# 14-Cypress.net
KiCad netlist of a schematic drawn in Altium Designer
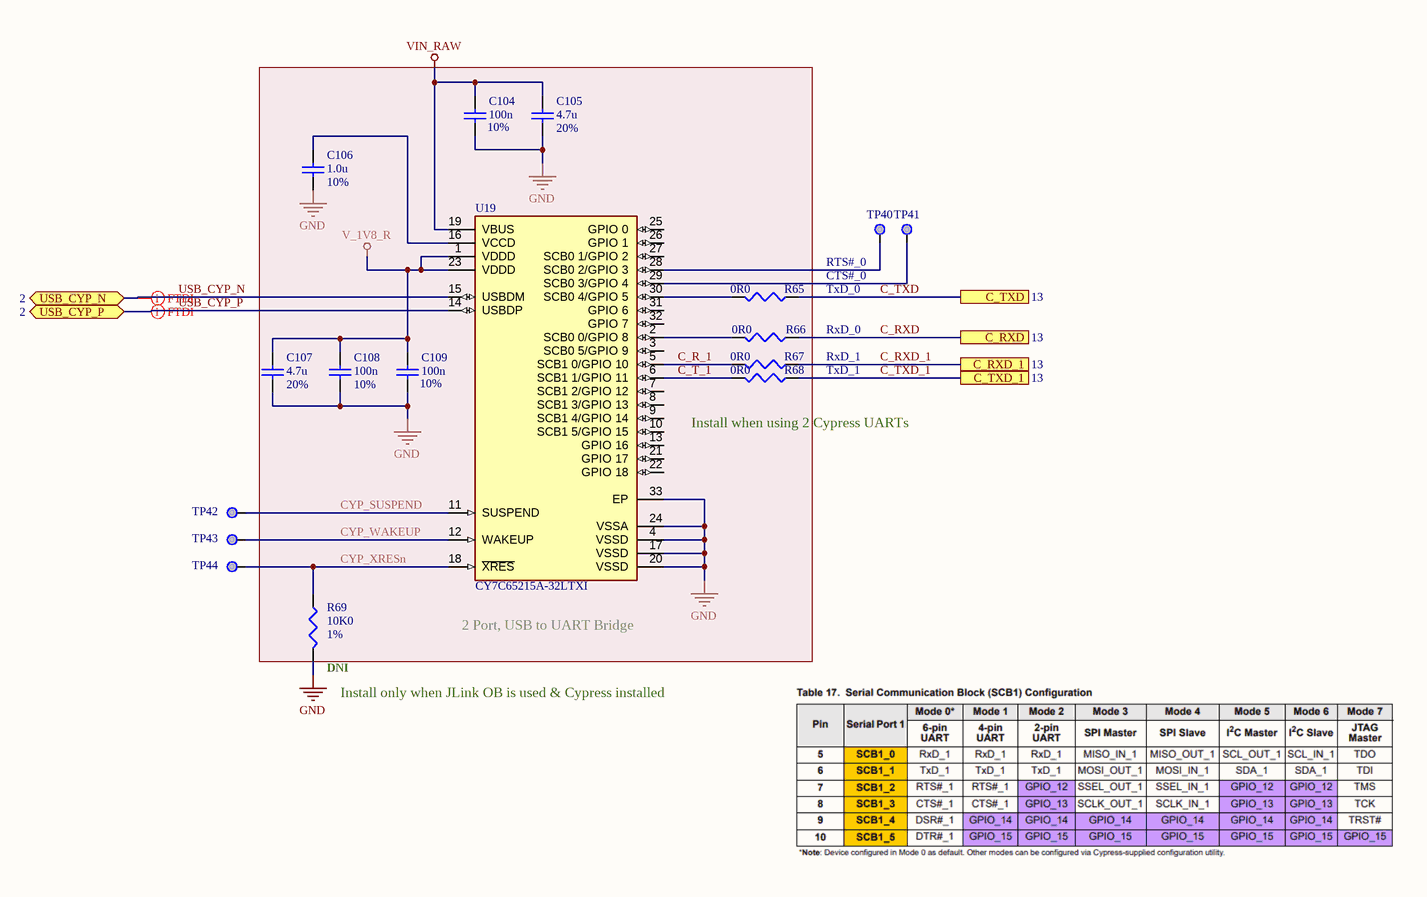
[diagram p0: 14-Cypress.SchDoc]

(export (version "E")
  (design (tool "Eeschema 10.0.6"))
  (components
    (comp (ref "C104")
      (value "100n")
      (footprint "CAPC0402-01")
      (description "DNI,Cap,100nF,10%,50V,X7R,0402")
      (fields
        (field (name "VOLTAGE") "50V")
        (field (name "TOLERANCE") "10%")
        (field (name "Comment") "Cap")
        (field (name "PUBLISHER") "Altium Limited")
      )
      (libsource (lib "kb1") (part "Cap"))
    )
    (comp (ref "C105")
      (value "4.7u")
      (footprint "CAPC0402-01")
      (description "DNI,Cap,4.7uF,20%,10V,X5R,0402")
      (fields
        (field (name "VOLTAGE") "10V")
        (field (name "TOLERANCE") "20%")
        (field (name "Comment") "Cap")
        (field (name "PUBLISHER") "Altium Limited")
      )
      (libsource (lib "Alif-2") (part "Cap_225M25VX5R0402_1"))
    )
    (comp (ref "C106")
      (value "1.0u")
      (footprint "CAPC0402-01")
      (description "DNI,Cap,1.0uF,20%,25V,X5R,0402")
      (fields
        (field (name "VOLTAGE") "25V")
        (field (name "TOLERANCE") "10%")
        (field (name "Comment") "Cap")
        (field (name "PUBLISHER") "Altium Limited")
      )
      (libsource (lib "kb1") (part "Cap"))
    )
    (comp (ref "C107")
      (value "4.7u")
      (footprint "CAPC0402-01")
      (description "DNI,Cap,4.7uF,20%,10V,X5R,0402")
      (fields
        (field (name "VOLTAGE") "10V")
        (field (name "TOLERANCE") "20%")
        (field (name "Comment") "Cap")
        (field (name "PUBLISHER") "Altium Limited")
      )
      (libsource (lib "Alif-2") (part "Cap_225M25VX5R0402_1"))
    )
    (comp (ref "C108")
      (value "100n")
      (footprint "CAPC0402-01")
      (description "DNI,Cap,100nF,10%,50V,X7R,0402")
      (fields
        (field (name "VOLTAGE") "50V")
        (field (name "TOLERANCE") "10%")
        (field (name "Comment") "Cap")
        (field (name "PUBLISHER") "Altium Limited")
      )
      (libsource (lib "kb1") (part "Cap"))
    )
    (comp (ref "C109")
      (value "100n")
      (footprint "CAPC0402-01")
      (description "DNI,Cap,100nF,10%,50V,X7R,0402")
      (fields
        (field (name "VOLTAGE") "50V")
        (field (name "TOLERANCE") "10%")
        (field (name "Comment") "Cap")
        (field (name "PUBLISHER") "Altium Limited")
      )
      (libsource (lib "kb1") (part "Cap"))
    )
    (comp (ref "R65")
      (value "0R0")
      (footprint "RESC0402-01")
      (description "DNI,Res,0R ohm,Jumper,0402")
      (fields
        (field (name "TOLERANCE") "JMPR")
        (field (name "Comment") "Res3")
        (field (name "PUBLISHER") "Altium Limited")
      )
      (libsource (lib "kb1") (part "Res3"))
    )
    (comp (ref "R66")
      (value "0R0")
      (footprint "RESC0402-01")
      (description "DNI,Res,0R ohm,Jumper,0402")
      (fields
        (field (name "TOLERANCE") "JMPR")
        (field (name "Comment") "Res3")
        (field (name "PUBLISHER") "Altium Limited")
      )
      (libsource (lib "kb1") (part "Res3"))
    )
    (comp (ref "R67")
      (value "0R0")
      (footprint "RESC0402-01")
      (description "DNI,Res,0R ohm,Jumper,0402")
      (fields
        (field (name "TOLERANCE") "JMPR")
        (field (name "Comment") "Res3")
        (field (name "PUBLISHER") "Altium Limited")
      )
      (libsource (lib "kb1") (part "Res3"))
    )
    (comp (ref "R68")
      (value "0R0")
      (footprint "RESC0402-01")
      (description "DNI,Res,0R ohm,Jumper,0402")
      (fields
        (field (name "TOLERANCE") "JMPR")
        (field (name "Comment") "Res3")
        (field (name "PUBLISHER") "Altium Limited")
      )
      (libsource (lib "kb1") (part "Res3"))
    )
    (comp (ref "R69")
      (value "10K0")
      (footprint "RESC0402-01")
      (description "DNI,Res,10K0,1%,100ppm,0402")
      (fields
        (field (name "TOLERANCE") "1%")
        (field (name "Comment") "Res3")
        (field (name "PUBLISHER") "Altium Limited")
      )
      (libsource (lib "kb1") (part "Res3"))
    )
    (comp (ref "TP40")
      (value "TP_SMPAD")
      (footprint "TP_50_RND")
      (description "DNI,Test Point, SMT Pad,--not a BOM item--")
      (libsource (lib "Alif-2") (part "TP_SMPAD"))
    )
    (comp (ref "TP41")
      (value "TP_SMPAD")
      (footprint "TP_50_RND")
      (description "DNI,Test Point, SMT Pad,--not a BOM item--")
      (libsource (lib "Alif-2") (part "TP_SMPAD"))
    )
    (comp (ref "TP42")
      (value "TP_SMPAD")
      (footprint "TP_50_RND")
      (description "DNI,Test Point, SMT Pad,--not a BOM item--")
      (libsource (lib "Alif-2") (part "TP_SMPAD"))
    )
    (comp (ref "TP43")
      (value "TP_SMPAD")
      (footprint "TP_50_RND")
      (description "DNI,Test Point, SMT Pad,--not a BOM item--")
      (libsource (lib "Alif-2") (part "TP_SMPAD"))
    )
    (comp (ref "TP44")
      (value "TP_SMPAD")
      (footprint "TP_50_RND")
      (description "DNI,Test Point, SMT Pad,--not a BOM item--")
      (libsource (lib "Alif-2") (part "TP_SMPAD"))
    )
    (comp (ref "U19")
      (value "CY7C65215A-32LTXI")
      (footprint "QFN32_5x5x1-0p5_INF-M_no3D")
      (description "DNI,IC,Dual USB to Serial Bridge,32QFN")
      (fields
        (field (name "OCTOPART") "https://octopart.com/cy7c65215-32ltxi-cypress+semiconductor-30243522")
      )
      (libsource (lib "Alif-2") (part "IC_Dual_USB_UART_Bridge"))
    )
  )
  (nets
    (net (code "1") (name "/CYP_SUSPEND") (class "Default")
      (node (ref "TP42") (pin "1") (pinfunction "1_1") (pintype "passive"))
      (node (ref "U19") (pin "11") (pinfunction "SUSPEND_11") (pintype "input"))
    )
    (net (code "2") (name "/CYP_WAKEUP") (class "Default")
      (node (ref "TP43") (pin "1") (pinfunction "1_1") (pintype "passive"))
      (node (ref "U19") (pin "12") (pinfunction "WAKEUP_12") (pintype "input"))
    )
    (net (code "3") (name "/CYP_XRESn") (class "Default")
      (node (ref "R69") (pin "1") (pinfunction "1_1") (pintype "passive"))
      (node (ref "TP44") (pin "1") (pinfunction "1_1") (pintype "passive"))
      (node (ref "U19") (pin "18") (pinfunction "~{XRES}_18") (pintype "input"))
    )
    (net (code "4") (name "/C_RXD") (class "Default")
      (node (ref "R66") (pin "1") (pinfunction "1_1") (pintype "passive"))
    )
    (net (code "5") (name "/C_RXD_1") (class "Default")
      (node (ref "R67") (pin "1") (pinfunction "1_1") (pintype "passive"))
    )
    (net (code "6") (name "/C_R_1") (class "Default")
      (node (ref "R67") (pin "2") (pinfunction "2_2") (pintype "passive"))
      (node (ref "U19") (pin "5") (pinfunction "SCB1_0/GPIO_10_5") (pintype "bidirectional"))
    )
    (net (code "7") (name "/C_TXD") (class "Default")
      (node (ref "R65") (pin "1") (pinfunction "1_1") (pintype "passive"))
    )
    (net (code "8") (name "/C_TXD_1") (class "Default")
      (node (ref "R68") (pin "1") (pinfunction "1_1") (pintype "passive"))
    )
    (net (code "9") (name "/C_T_1") (class "Default")
      (node (ref "R68") (pin "2") (pinfunction "2_2") (pintype "passive"))
      (node (ref "U19") (pin "6") (pinfunction "SCB1_1/GPIO_11_6") (pintype "bidirectional"))
    )
    (net (code "10") (name "/USB_CYP_N") (class "Default")
      (node (ref "U19") (pin "15") (pinfunction "USBDM_15") (pintype "bidirectional"))
    )
    (net (code "11") (name "/USB_CYP_P") (class "Default")
      (node (ref "U19") (pin "14") (pinfunction "USBDP_14") (pintype "bidirectional"))
    )
    (net (code "12") (name "GND") (class "Default")
      (node (ref "C104") (pin "1") (pinfunction "1_1") (pintype "passive"))
      (node (ref "C105") (pin "1") (pinfunction "1_1") (pintype "passive"))
      (node (ref "C106") (pin "1") (pinfunction "1_1") (pintype "passive"))
      (node (ref "C107") (pin "1") (pinfunction "1_1") (pintype "passive"))
      (node (ref "C108") (pin "1") (pinfunction "1_1") (pintype "passive"))
      (node (ref "C109") (pin "1") (pinfunction "1_1") (pintype "passive"))
      (node (ref "R69") (pin "2") (pinfunction "2_2") (pintype "passive"))
      (node (ref "U19") (pin "17") (pinfunction "VSSD_17") (pintype "power_in"))
      (node (ref "U19") (pin "20") (pinfunction "VSSD_20") (pintype "power_in"))
      (node (ref "U19") (pin "24") (pinfunction "VSSA_24") (pintype "power_in"))
      (node (ref "U19") (pin "33") (pinfunction "EP_33") (pintype "power_in"))
      (node (ref "U19") (pin "4") (pinfunction "VSSD_4") (pintype "power_in"))
    )
    (net (code "13") (name "Net-(U19-SCB0_0{slash}GPIO_8)") (class "Default")
      (node (ref "R66") (pin "2") (pinfunction "2_2") (pintype "passive"))
      (node (ref "U19") (pin "2") (pinfunction "SCB0_0/GPIO_8_2") (pintype "bidirectional"))
    )
    (net (code "14") (name "Net-(U19-SCB0_2{slash}GPIO_3)") (class "Default")
      (node (ref "TP40") (pin "1") (pinfunction "1_1") (pintype "passive"))
      (node (ref "U19") (pin "28") (pinfunction "SCB0_2/GPIO_3_28") (pintype "bidirectional"))
    )
    (net (code "15") (name "Net-(U19-SCB0_3{slash}GPIO_4)") (class "Default")
      (node (ref "TP41") (pin "1") (pinfunction "1_1") (pintype "passive"))
      (node (ref "U19") (pin "29") (pinfunction "SCB0_3/GPIO_4_29") (pintype "bidirectional"))
    )
    (net (code "16") (name "Net-(U19-SCB0_4{slash}GPIO_5)") (class "Default")
      (node (ref "R65") (pin "2") (pinfunction "2_2") (pintype "passive"))
      (node (ref "U19") (pin "30") (pinfunction "SCB0_4/GPIO_5_30") (pintype "bidirectional"))
    )
    (net (code "17") (name "Net-(U19-VCCD)") (class "Default")
      (node (ref "C106") (pin "2") (pinfunction "2_2") (pintype "passive"))
      (node (ref "U19") (pin "16") (pinfunction "VCCD_16") (pintype "power_in"))
    )
    (net (code "18") (name "VIN_RAW") (class "Default")
      (node (ref "C104") (pin "2") (pinfunction "2_2") (pintype "passive"))
      (node (ref "C105") (pin "2") (pinfunction "2_2") (pintype "passive"))
      (node (ref "U19") (pin "19") (pinfunction "VBUS_19") (pintype "power_in"))
    )
    (net (code "19") (name "V_1V8_R") (class "Default")
      (node (ref "C107") (pin "2") (pinfunction "2_2") (pintype "passive"))
      (node (ref "C108") (pin "2") (pinfunction "2_2") (pintype "passive"))
      (node (ref "C109") (pin "2") (pinfunction "2_2") (pintype "passive"))
      (node (ref "U19") (pin "1") (pinfunction "VDDD_1") (pintype "power_in"))
      (node (ref "U19") (pin "23") (pinfunction "VDDD_23") (pintype "power_in"))
    )
    (net (code "20") (name "unconnected-(U19-GPIO_0-Pad25)") (class "Default")
      (node (ref "U19") (pin "25") (pinfunction "GPIO_0_25") (pintype "bidirectional"))
    )
    (net (code "21") (name "unconnected-(U19-GPIO_1-Pad26)") (class "Default")
      (node (ref "U19") (pin "26") (pinfunction "GPIO_1_26") (pintype "bidirectional"))
    )
    (net (code "22") (name "unconnected-(U19-GPIO_6-Pad31)") (class "Default")
      (node (ref "U19") (pin "31") (pinfunction "GPIO_6_31") (pintype "bidirectional"))
    )
    (net (code "23") (name "unconnected-(U19-GPIO_7-Pad32)") (class "Default")
      (node (ref "U19") (pin "32") (pinfunction "GPIO_7_32") (pintype "bidirectional"))
    )
    (net (code "24") (name "unconnected-(U19-GPIO_16-Pad13)") (class "Default")
      (node (ref "U19") (pin "13") (pinfunction "GPIO_16_13") (pintype "bidirectional"))
    )
    (net (code "25") (name "unconnected-(U19-GPIO_17-Pad21)") (class "Default")
      (node (ref "U19") (pin "21") (pinfunction "GPIO_17_21") (pintype "bidirectional"))
    )
    (net (code "26") (name "unconnected-(U19-GPIO_18-Pad22)") (class "Default")
      (node (ref "U19") (pin "22") (pinfunction "GPIO_18_22") (pintype "bidirectional"))
    )
    (net (code "27") (name "unconnected-(U19-SCB0_1{slash}GPIO_2-Pad27)") (class "Default")
      (node (ref "U19") (pin "27") (pinfunction "SCB0_1/GPIO_2_27") (pintype "bidirectional"))
    )
    (net (code "28") (name "unconnected-(U19-SCB0_5{slash}GPIO_9-Pad3)") (class "Default")
      (node (ref "U19") (pin "3") (pinfunction "SCB0_5/GPIO_9_3") (pintype "bidirectional"))
    )
    (net (code "29") (name "unconnected-(U19-SCB1_2{slash}GPIO_12-Pad7)") (class "Default")
      (node (ref "U19") (pin "7") (pinfunction "SCB1_2/GPIO_12_7") (pintype "bidirectional"))
    )
    (net (code "30") (name "unconnected-(U19-SCB1_3{slash}GPIO_13-Pad8)") (class "Default")
      (node (ref "U19") (pin "8") (pinfunction "SCB1_3/GPIO_13_8") (pintype "bidirectional"))
    )
    (net (code "31") (name "unconnected-(U19-SCB1_4{slash}GPIO_14-Pad9)") (class "Default")
      (node (ref "U19") (pin "9") (pinfunction "SCB1_4/GPIO_14_9") (pintype "bidirectional"))
    )
    (net (code "32") (name "unconnected-(U19-SCB1_5{slash}GPIO_15-Pad10)") (class "Default")
      (node (ref "U19") (pin "10") (pinfunction "SCB1_5/GPIO_15_10") (pintype "bidirectional"))
    )
  )
)
